# CARduino.net
KiCad netlist of a schematic drawn in EAGLE
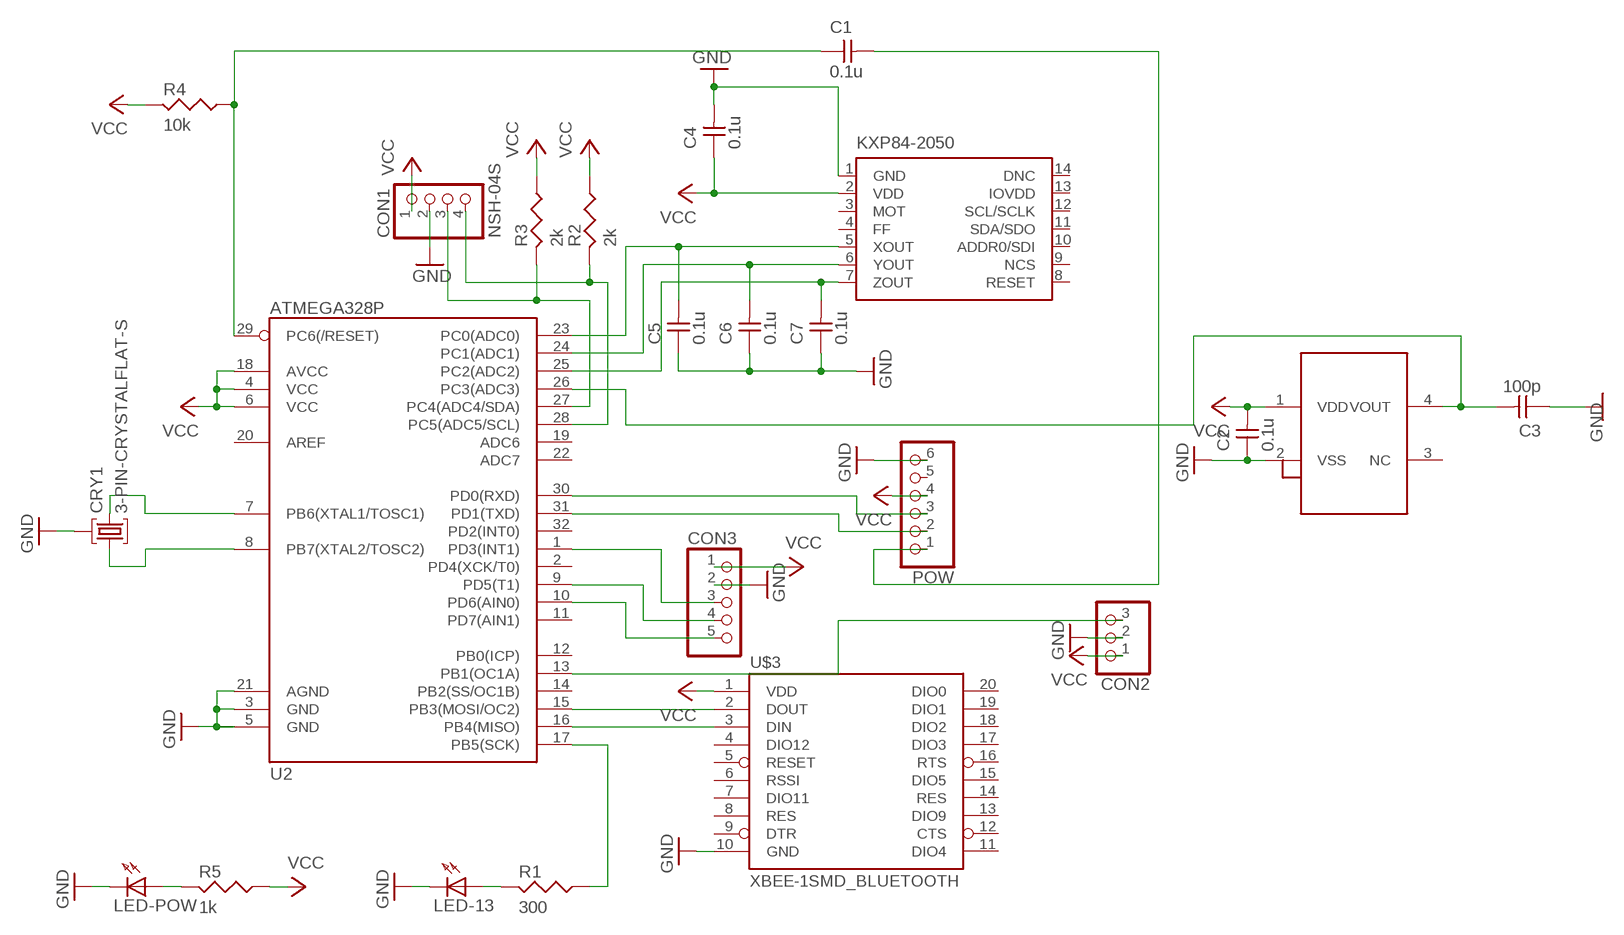
[diagram p0: schematic, sheet 1]

(export (version "E")
  (design (tool "Eeschema 10.0.6"))
  (components
    (comp (ref "C1")
      (value "0.1u")
      (footprint "eagle-import:1608")
      (libsource (lib "eagle-import") (part "1608"))
    )
    (comp (ref "C2")
      (value "0.1u")
      (footprint "eagle-import:1608")
      (libsource (lib "eagle-import") (part "1608"))
    )
    (comp (ref "C3")
      (value "100p")
      (footprint "eagle-import:1608")
      (libsource (lib "eagle-import") (part "1608"))
    )
    (comp (ref "C4")
      (value "0.1u")
      (footprint "eagle-import:1608")
      (libsource (lib "eagle-import") (part "1608"))
    )
    (comp (ref "C5")
      (value "0.1u")
      (footprint "eagle-import:1608")
      (libsource (lib "eagle-import") (part "1608"))
    )
    (comp (ref "C6")
      (value "0.1u")
      (footprint "eagle-import:1608")
      (libsource (lib "eagle-import") (part "1608"))
    )
    (comp (ref "C7")
      (value "0.1u")
      (footprint "eagle-import:1608")
      (libsource (lib "eagle-import") (part "1608"))
    )
    (comp (ref "CON1")
      (value "NSH-04S")
      (footprint "eagle-import:NSH-04-S")
      (libsource (lib "eagle-import") (part "NSH-04S"))
    )
    (comp (ref "CON2")
      (value "NSH-03S")
      (footprint "eagle-import:NSH-03-S")
      (libsource (lib "eagle-import") (part "NSH-03S"))
    )
    (comp (ref "CON3")
      (value "PINHD-1X5DIP")
      (footprint "eagle-import:1X05")
      (libsource (lib "eagle-import") (part "PINHD-1X5DIP"))
    )
    (comp (ref "CRY1")
      (value "3-PIN-CRYSTALFLAT-S")
      (footprint "eagle-import:CRYSTAL-CSTCE8M")
      (libsource (lib "eagle-import") (part "3-PIN-CRYSTALFLAT-S"))
    )
    (comp (ref "LED-13")
      (value "1608")
      (footprint "eagle-import:1608")
      (libsource (lib "eagle-import") (part "06_led_1608"))
    )
    (comp (ref "LED-POW")
      (value "1608")
      (footprint "eagle-import:1608")
      (libsource (lib "eagle-import") (part "06_led_1608"))
    )
    (comp (ref "POW")
      (value "PINHD-1X6NORMAL")
      (footprint "eagle-import:1X06")
      (libsource (lib "eagle-import") (part "PINHD-1X6NORMAL"))
    )
    (comp (ref "R1")
      (value "300")
      (footprint "eagle-import:1608")
      (libsource (lib "eagle-import") (part "02_resistor_1608"))
    )
    (comp (ref "R2")
      (value "2k")
      (footprint "eagle-import:1608")
      (libsource (lib "eagle-import") (part "02_resistor_1608"))
    )
    (comp (ref "R3")
      (value "2k")
      (footprint "eagle-import:1608")
      (libsource (lib "eagle-import") (part "02_resistor_1608"))
    )
    (comp (ref "R4")
      (value "10k")
      (footprint "eagle-import:1608")
      (libsource (lib "eagle-import") (part "02_resistor_1608"))
    )
    (comp (ref "R5")
      (value "1k")
      (footprint "eagle-import:1608")
      (libsource (lib "eagle-import") (part "02_resistor_1608"))
    )
    (comp (ref "S1")
      (value "TEMPERATURE-S8120C")
      (footprint "eagle-import:SC-82AB")
      (libsource (lib "eagle-import") (part "TEMPERATURE-S8120C"))
    )
    (comp (ref "U$1")
      (value "KXP84-2050")
      (footprint "eagle-import:DFN14-5X5")
      (libsource (lib "eagle-import") (part "KXP84-2050"))
    )
    (comp (ref "U$3")
      (value "XBEE-1SMD_BLUETOOTH")
      (footprint "eagle-import:XBEE-SMD_BLUETOOTH")
      (libsource (lib "eagle-import") (part "XBEE-1SMD_BLUETOOTH"))
    )
    (comp (ref "U2")
      (value "ATMEGA328P")
      (footprint "eagle-import:TQFP32-08")
      (libsource (lib "eagle-import") (part "ATMEGA328_SMT"))
    )
  )
  (nets
    (net (code "1") (name "/IOVDD") (class "Default")
      (node (ref "U$1") (pin "13") (pinfunction "IOVDD_13") (pintype "power_in"))
    )
    (net (code "2") (name "GND") (class "Default")
      (node (ref "C2") (pin "P$1") (pinfunction "1_P$1") (pintype "passive"))
      (node (ref "C3") (pin "P$1") (pinfunction "1_P$1") (pintype "passive"))
      (node (ref "C4") (pin "P$2") (pinfunction "2_P$2") (pintype "passive"))
      (node (ref "C5") (pin "P$1") (pinfunction "1_P$1") (pintype "passive"))
      (node (ref "C6") (pin "P$1") (pinfunction "1_P$1") (pintype "passive"))
      (node (ref "C7") (pin "P$1") (pinfunction "1_P$1") (pintype "passive"))
      (node (ref "CON1") (pin "2") (pinfunction "2_2") (pintype "passive"))
      (node (ref "CON2") (pin "2") (pinfunction "2_2") (pintype "passive"))
      (node (ref "CON3") (pin "2") (pinfunction "2_2") (pintype "passive"))
      (node (ref "CRY1") (pin "G") (pinfunction "GND_G") (pintype "passive"))
      (node (ref "LED-13") (pin "C") (pinfunction "C_C") (pintype "passive"))
      (node (ref "LED-POW") (pin "C") (pinfunction "C_C") (pintype "passive"))
      (node (ref "POW") (pin "6") (pinfunction "6_6") (pintype "passive"))
      (node (ref "S1") (pin "2") (pinfunction "VSS_2") (pintype "bidirectional"))
      (node (ref "U$1") (pin "1") (pinfunction "GND_1") (pintype "power_in"))
      (node (ref "U$3") (pin "10") (pinfunction "GND_10") (pintype "power_in"))
      (node (ref "U2") (pin "21") (pinfunction "AGND_21") (pintype "bidirectional"))
      (node (ref "U2") (pin "3") (pinfunction "GND_3") (pintype "bidirectional"))
      (node (ref "U2") (pin "5") (pinfunction "GND_5") (pintype "bidirectional"))
    )
    (net (code "3") (name "Net-(C1-1)") (class "Default")
      (node (ref "C1") (pin "P$1") (pinfunction "1_P$1") (pintype "passive"))
      (node (ref "R4") (pin "1") (pinfunction "1_1") (pintype "passive"))
      (node (ref "U2") (pin "29") (pinfunction "PC6(/RESET)_29") (pintype "bidirectional"))
    )
    (net (code "4") (name "Net-(C1-2)") (class "Default")
      (node (ref "C1") (pin "P$2") (pinfunction "2_P$2") (pintype "passive"))
      (node (ref "POW") (pin "1") (pinfunction "1_1") (pintype "passive"))
    )
    (net (code "5") (name "Net-(C3-2)") (class "Default")
      (node (ref "C3") (pin "P$2") (pinfunction "2_P$2") (pintype "passive"))
      (node (ref "S1") (pin "4") (pinfunction "VOUT_4") (pintype "bidirectional"))
      (node (ref "U2") (pin "26") (pinfunction "PC3(ADC3)_26") (pintype "bidirectional"))
    )
    (net (code "6") (name "Net-(C5-2)") (class "Default")
      (node (ref "C5") (pin "P$2") (pinfunction "2_P$2") (pintype "passive"))
      (node (ref "U$1") (pin "5") (pinfunction "XOUT_5") (pintype "output"))
      (node (ref "U2") (pin "23") (pinfunction "PC0(ADC0)_23") (pintype "bidirectional"))
    )
    (net (code "7") (name "Net-(C6-2)") (class "Default")
      (node (ref "C6") (pin "P$2") (pinfunction "2_P$2") (pintype "passive"))
      (node (ref "U$1") (pin "6") (pinfunction "YOUT_6") (pintype "output"))
      (node (ref "U2") (pin "24") (pinfunction "PC1(ADC1)_24") (pintype "bidirectional"))
    )
    (net (code "8") (name "Net-(C7-2)") (class "Default")
      (node (ref "C7") (pin "P$2") (pinfunction "2_P$2") (pintype "passive"))
      (node (ref "U$1") (pin "7") (pinfunction "ZOUT_7") (pintype "output"))
      (node (ref "U2") (pin "25") (pinfunction "PC2(ADC2)_25") (pintype "bidirectional"))
    )
    (net (code "9") (name "Net-(CRY1-1)") (class "Default")
      (node (ref "CRY1") (pin "O1") (pinfunction "1_O1") (pintype "passive"))
      (node (ref "U2") (pin "8") (pinfunction "PB7(XTAL2/TOSC2)_8") (pintype "bidirectional"))
    )
    (net (code "10") (name "Net-(CRY1-2)") (class "Default")
      (node (ref "CRY1") (pin "O2") (pinfunction "2_O2") (pintype "passive"))
      (node (ref "U2") (pin "7") (pinfunction "PB6(XTAL1/TOSC1)_7") (pintype "bidirectional"))
    )
    (net (code "11") (name "Net-(LED-13-PadA)") (class "Default")
      (node (ref "LED-13") (pin "A") (pinfunction "A_A") (pintype "passive"))
      (node (ref "R1") (pin "2") (pinfunction "2_2") (pintype "passive"))
    )
    (net (code "12") (name "Net-(LED-POW-PadA)") (class "Default")
      (node (ref "LED-POW") (pin "A") (pinfunction "A_A") (pintype "passive"))
      (node (ref "R5") (pin "2") (pinfunction "2_2") (pintype "passive"))
    )
    (net (code "13") (name "Net-(U$3-DIN)") (class "Default")
      (node (ref "U$3") (pin "3") (pinfunction "DIN_3") (pintype "input"))
      (node (ref "U2") (pin "16") (pinfunction "PB4(MISO)_16") (pintype "bidirectional"))
    )
    (net (code "14") (name "Net-(U$3-DOUT)") (class "Default")
      (node (ref "U$3") (pin "2") (pinfunction "DOUT_2") (pintype "output"))
      (node (ref "U2") (pin "15") (pinfunction "PB3(MOSI/OC2)_15") (pintype "bidirectional"))
    )
    (net (code "15") (name "Net-(U2-PB1(OC1A))") (class "Default")
      (node (ref "CON2") (pin "3") (pinfunction "3_3") (pintype "passive"))
      (node (ref "U2") (pin "13") (pinfunction "PB1(OC1A)_13") (pintype "bidirectional"))
    )
    (net (code "16") (name "Net-(U2-PB5(SCK))") (class "Default")
      (node (ref "R1") (pin "1") (pinfunction "1_1") (pintype "passive"))
      (node (ref "U2") (pin "17") (pinfunction "PB5(SCK)_17") (pintype "bidirectional"))
    )
    (net (code "17") (name "Net-(U2-PC4(ADC4{slash}SDA))") (class "Default")
      (node (ref "CON1") (pin "3") (pinfunction "3_3") (pintype "passive"))
      (node (ref "R3") (pin "2") (pinfunction "2_2") (pintype "passive"))
      (node (ref "U2") (pin "27") (pinfunction "PC4(ADC4/SDA)_27") (pintype "bidirectional"))
    )
    (net (code "18") (name "Net-(U2-PC5(ADC5{slash}SCL))") (class "Default")
      (node (ref "CON1") (pin "4") (pinfunction "4_4") (pintype "passive"))
      (node (ref "R2") (pin "2") (pinfunction "2_2") (pintype "passive"))
      (node (ref "U2") (pin "28") (pinfunction "PC5(ADC5/SCL)_28") (pintype "bidirectional"))
    )
    (net (code "19") (name "Net-(U2-PD0(RXD))") (class "Default")
      (node (ref "POW") (pin "3") (pinfunction "3_3") (pintype "passive"))
      (node (ref "U2") (pin "30") (pinfunction "PD0(RXD)_30") (pintype "bidirectional"))
    )
    (net (code "20") (name "Net-(U2-PD1(TXD))") (class "Default")
      (node (ref "POW") (pin "2") (pinfunction "2_2") (pintype "passive"))
      (node (ref "U2") (pin "31") (pinfunction "PD1(TXD)_31") (pintype "bidirectional"))
    )
    (net (code "21") (name "Net-(U2-PD3(INT1))") (class "Default")
      (node (ref "CON3") (pin "3") (pinfunction "3_3") (pintype "passive"))
      (node (ref "U2") (pin "1") (pinfunction "PD3(INT1)_1") (pintype "bidirectional"))
    )
    (net (code "22") (name "Net-(U2-PD5(T1))") (class "Default")
      (node (ref "CON3") (pin "4") (pinfunction "4_4") (pintype "passive"))
      (node (ref "U2") (pin "9") (pinfunction "PD5(T1)_9") (pintype "bidirectional"))
    )
    (net (code "23") (name "Net-(U2-PD6(AIN0))") (class "Default")
      (node (ref "CON3") (pin "5") (pinfunction "5_5") (pintype "passive"))
      (node (ref "U2") (pin "10") (pinfunction "PD6(AIN0)_10") (pintype "bidirectional"))
    )
    (net (code "24") (name "VCC") (class "Default")
      (node (ref "C2") (pin "P$2") (pinfunction "2_P$2") (pintype "passive"))
      (node (ref "C4") (pin "P$1") (pinfunction "1_P$1") (pintype "passive"))
      (node (ref "CON1") (pin "1") (pinfunction "1_1") (pintype "passive"))
      (node (ref "CON2") (pin "1") (pinfunction "1_1") (pintype "passive"))
      (node (ref "CON3") (pin "1") (pinfunction "1_1") (pintype "passive"))
      (node (ref "POW") (pin "4") (pinfunction "4_4") (pintype "passive"))
      (node (ref "R2") (pin "1") (pinfunction "1_1") (pintype "passive"))
      (node (ref "R3") (pin "1") (pinfunction "1_1") (pintype "passive"))
      (node (ref "R4") (pin "2") (pinfunction "2_2") (pintype "passive"))
      (node (ref "R5") (pin "1") (pinfunction "1_1") (pintype "passive"))
      (node (ref "S1") (pin "1") (pinfunction "VDD_1") (pintype "bidirectional"))
      (node (ref "U$1") (pin "2") (pinfunction "VDD_2") (pintype "power_in"))
      (node (ref "U$3") (pin "1") (pinfunction "VDD_1") (pintype "power_in"))
      (node (ref "U2") (pin "18") (pinfunction "AVCC_18") (pintype "bidirectional"))
      (node (ref "U2") (pin "4") (pinfunction "VCC_4") (pintype "bidirectional"))
      (node (ref "U2") (pin "6") (pinfunction "VCC_6") (pintype "bidirectional"))
    )
    (net (code "25") (name "unconnected-(POW-Pad5)") (class "Default")
      (node (ref "POW") (pin "5") (pinfunction "5_5") (pintype "passive"))
    )
    (net (code "26") (name "unconnected-(S1-NC-Pad3)") (class "Default")
      (node (ref "S1") (pin "3") (pinfunction "NC_3") (pintype "bidirectional"))
    )
    (net (code "27") (name "unconnected-(U$1-ADDR0{slash}SDI-Pad10)") (class "Default")
      (node (ref "U$1") (pin "10") (pinfunction "ADDR0/SDI_10") (pintype "input"))
    )
    (net (code "28") (name "unconnected-(U$1-DNC-Pad14)") (class "Default")
      (node (ref "U$1") (pin "14") (pinfunction "DNC_14") (pintype "no_connect"))
    )
    (net (code "29") (name "unconnected-(U$1-FF-Pad4)") (class "Default")
      (node (ref "U$1") (pin "4") (pinfunction "FF_4") (pintype "input"))
    )
    (net (code "30") (name "unconnected-(U$1-MOT-Pad3)") (class "Default")
      (node (ref "U$1") (pin "3") (pinfunction "MOT_3") (pintype "input"))
    )
    (net (code "31") (name "unconnected-(U$1-NCS-Pad9)") (class "Default")
      (node (ref "U$1") (pin "9") (pinfunction "NCS_9") (pintype "bidirectional"))
    )
    (net (code "32") (name "unconnected-(U$1-RESET-Pad8)") (class "Default")
      (node (ref "U$1") (pin "8") (pinfunction "RESET_8") (pintype "input"))
    )
    (net (code "33") (name "unconnected-(U$1-SCL{slash}SCLK-Pad12)") (class "Default")
      (node (ref "U$1") (pin "12") (pinfunction "SCL/SCLK_12") (pintype "input"))
    )
    (net (code "34") (name "unconnected-(U$1-SDA{slash}SDO-Pad11)") (class "Default")
      (node (ref "U$1") (pin "11") (pinfunction "SDA/SDO_11") (pintype "input"))
    )
    (net (code "35") (name "unconnected-(U$3-CTS-Pad12)") (class "Default")
      (node (ref "U$3") (pin "12") (pinfunction "CTS_12") (pintype "output"))
    )
    (net (code "36") (name "unconnected-(U$3-DIO0-Pad20)") (class "Default")
      (node (ref "U$3") (pin "20") (pinfunction "DIO0_20") (pintype "bidirectional"))
    )
    (net (code "37") (name "unconnected-(U$3-DIO1-Pad19)") (class "Default")
      (node (ref "U$3") (pin "19") (pinfunction "DIO1_19") (pintype "bidirectional"))
    )
    (net (code "38") (name "unconnected-(U$3-DIO2-Pad18)") (class "Default")
      (node (ref "U$3") (pin "18") (pinfunction "DIO2_18") (pintype "bidirectional"))
    )
    (net (code "39") (name "unconnected-(U$3-DIO3-Pad17)") (class "Default")
      (node (ref "U$3") (pin "17") (pinfunction "DIO3_17") (pintype "bidirectional"))
    )
    (net (code "40") (name "unconnected-(U$3-DIO4-Pad11)") (class "Default")
      (node (ref "U$3") (pin "11") (pinfunction "DIO4_11") (pintype "bidirectional"))
    )
    (net (code "41") (name "unconnected-(U$3-DIO5-Pad15)") (class "Default")
      (node (ref "U$3") (pin "15") (pinfunction "DIO5_15") (pintype "bidirectional"))
    )
    (net (code "42") (name "unconnected-(U$3-DIO9-Pad13)") (class "Default")
      (node (ref "U$3") (pin "13") (pinfunction "DIO9_13") (pintype "bidirectional"))
    )
    (net (code "43") (name "unconnected-(U$3-DIO11-Pad7)") (class "Default")
      (node (ref "U$3") (pin "7") (pinfunction "DIO11_7") (pintype "bidirectional"))
    )
    (net (code "44") (name "unconnected-(U$3-DIO12-Pad4)") (class "Default")
      (node (ref "U$3") (pin "4") (pinfunction "DIO12_4") (pintype "bidirectional"))
    )
    (net (code "45") (name "unconnected-(U$3-DTR-Pad9)") (class "Default")
      (node (ref "U$3") (pin "9") (pinfunction "DTR_9") (pintype "bidirectional"))
    )
    (net (code "46") (name "unconnected-(U$3-RES-Pad8)") (class "Default")
      (node (ref "U$3") (pin "8") (pinfunction "RES_8") (pintype "bidirectional"))
    )
    (net (code "47") (name "unconnected-(U$3-RES-Pad14)") (class "Default")
      (node (ref "U$3") (pin "14") (pinfunction "RES_14") (pintype "bidirectional"))
    )
    (net (code "48") (name "unconnected-(U$3-RESET-Pad5)") (class "Default")
      (node (ref "U$3") (pin "5") (pinfunction "RESET_5") (pintype "input"))
    )
    (net (code "49") (name "unconnected-(U$3-RSSI-Pad6)") (class "Default")
      (node (ref "U$3") (pin "6") (pinfunction "RSSI_6") (pintype "bidirectional"))
    )
    (net (code "50") (name "unconnected-(U$3-RTS-Pad16)") (class "Default")
      (node (ref "U$3") (pin "16") (pinfunction "RTS_16") (pintype "input"))
    )
    (net (code "51") (name "unconnected-(U2-ADC6-Pad19)") (class "Default")
      (node (ref "U2") (pin "19") (pinfunction "ADC6_19") (pintype "bidirectional"))
    )
    (net (code "52") (name "unconnected-(U2-ADC7-Pad22)") (class "Default")
      (node (ref "U2") (pin "22") (pinfunction "ADC7_22") (pintype "bidirectional"))
    )
    (net (code "53") (name "unconnected-(U2-AREF-Pad20)") (class "Default")
      (node (ref "U2") (pin "20") (pinfunction "AREF_20") (pintype "bidirectional"))
    )
    (net (code "54") (name "unconnected-(U2-PB0(ICP)-Pad12)") (class "Default")
      (node (ref "U2") (pin "12") (pinfunction "PB0(ICP)_12") (pintype "bidirectional"))
    )
    (net (code "55") (name "unconnected-(U2-PB2(SS{slash}OC1B)-Pad14)") (class "Default")
      (node (ref "U2") (pin "14") (pinfunction "PB2(SS/OC1B)_14") (pintype "bidirectional"))
    )
    (net (code "56") (name "unconnected-(U2-PD2(INT0)-Pad32)") (class "Default")
      (node (ref "U2") (pin "32") (pinfunction "PD2(INT0)_32") (pintype "bidirectional"))
    )
    (net (code "57") (name "unconnected-(U2-PD4(XCK{slash}T0)-Pad2)") (class "Default")
      (node (ref "U2") (pin "2") (pinfunction "PD4(XCK/T0)_2") (pintype "bidirectional"))
    )
    (net (code "58") (name "unconnected-(U2-PD7(AIN1)-Pad11)") (class "Default")
      (node (ref "U2") (pin "11") (pinfunction "PD7(AIN1)_11") (pintype "bidirectional"))
    )
  )
)
